# key_pcb_assy_FPC.net
KiCad netlist of a schematic drawn in Altium Designer
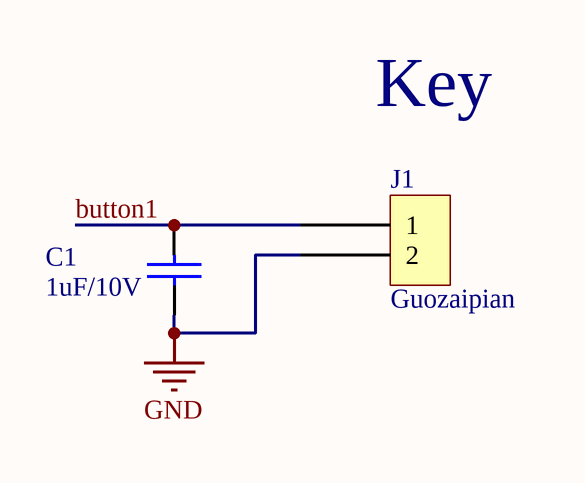
[diagram p0: key_pcb_assy FPC.SchDoc]

(export (version "E")
  (design (tool "Eeschema 10.0.6"))
  (components
    (comp (ref "C1")
      (value "1uF/10V")
      (footprint "0402C")
      (description "厂家：Murata，型号：GRM155R71A104KA01D")
      (libsource (lib "*") (part "CAP"))
    )
    (comp (ref "J1")
      (value "Guozaipian")
      (footprint "5MM GUOZHAIPIAN")
      (description "Guozaipian switch")
      (libsource (lib "*") (part "Guozaipian"))
    )
  )
  (nets
    (net (code "1") (name "/button1") (class "Default")
      (node (ref "C1") (pin "1") (pinfunction "1_1") (pintype "passive"))
      (node (ref "J1") (pin "1") (pinfunction "1_1") (pintype "passive"))
    )
    (net (code "2") (name "GND") (class "Default")
      (node (ref "C1") (pin "2") (pinfunction "2_2") (pintype "passive"))
      (node (ref "J1") (pin "2") (pinfunction "2_2") (pintype "passive"))
    )
  )
)
